# Colour_Detector.net
KiCad netlist of a schematic drawn in EAGLE
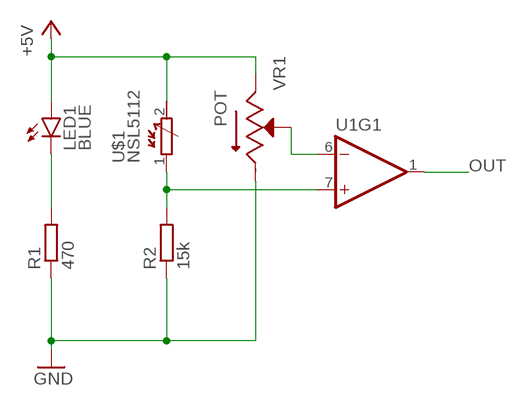
[diagram p0: schematic, sheet 1]

(export (version "E")
  (design (tool "Eeschema 10.0.6"))
  (components
    (comp (ref "LED1")
      (value "BLUE")
      (footprint "eagle-import:LED3MM")
      (libsource (lib "eagle-import") (part "LED_23MM"))
    )
    (comp (ref "R1")
      (value "470")
      (footprint "eagle-import:0204_7")
      (libsource (lib "eagle-import") (part "R-EU_0204/7"))
    )
    (comp (ref "R2")
      (value "15k")
      (footprint "eagle-import:0204_7")
      (libsource (lib "eagle-import") (part "R-EU_0204/7"))
    )
    (comp (ref "U$1")
      (value "NSL5112")
      (footprint "eagle-import:KK-156-2")
      (libsource (lib "eagle-import") (part "NSL5112"))
    )
    (comp (ref "U1")
      (value "LM339DIP")
      (footprint "eagle-import:DIL14")
      (libsource (lib "eagle-import") (part "LM339DIP"))
    )
    (comp (ref "VR1")
      (value "POT")
      (footprint "eagle-import:TRIM_3296W-1-250")
      (fields (field (name "MF") "Bourns") (field (name "MP") "3296W-1-250"))
      (libsource (lib "eagle-import") (part "POT"))
    )
  )
  (nets
    (net (code "1") (name "+5V") (class "Default")
      (node (ref "LED1") (pin "A") (pinfunction "A_A") (pintype "passive"))
      (node (ref "U$1") (pin "2") (pinfunction "E_2") (pintype "passive"))
      (node (ref "VR1") (pin "1") (pinfunction "CCW_1") (pintype "passive"))
    )
    (net (code "2") (name "/OUT") (class "Default")
      (node (ref "U1") (pin "1") (pinfunction "OUT_1") (pintype "output"))
    )
    (net (code "3") (name "GND") (class "Default")
      (node (ref "R1") (pin "1") (pinfunction "1_1") (pintype "passive"))
      (node (ref "R2") (pin "1") (pinfunction "1_1") (pintype "passive"))
      (node (ref "VR1") (pin "3") (pinfunction "CW_3") (pintype "passive"))
    )
    (net (code "4") (name "Net-(LED1-C)") (class "Default")
      (node (ref "LED1") (pin "K") (pinfunction "C_K") (pintype "passive"))
      (node (ref "R1") (pin "2") (pinfunction "2_2") (pintype "passive"))
    )
    (net (code "5") (name "Net-(U$1-A)") (class "Default")
      (node (ref "R2") (pin "2") (pinfunction "2_2") (pintype "passive"))
      (node (ref "U$1") (pin "1") (pinfunction "A_1") (pintype "passive"))
      (node (ref "U1") (pin "7") (pinfunction "+IN_7") (pintype "input"))
    )
    (net (code "6") (name "Net-(U1A--IN)") (class "Default")
      (node (ref "U1") (pin "6") (pinfunction "-IN_6") (pintype "input"))
      (node (ref "VR1") (pin "2") (pinfunction "WIPER_2") (pintype "passive"))
    )
  )
)
